# PSPS_AVNC_SRD_power-2020-10-14.net
KiCad netlist of a schematic drawn in EAGLE
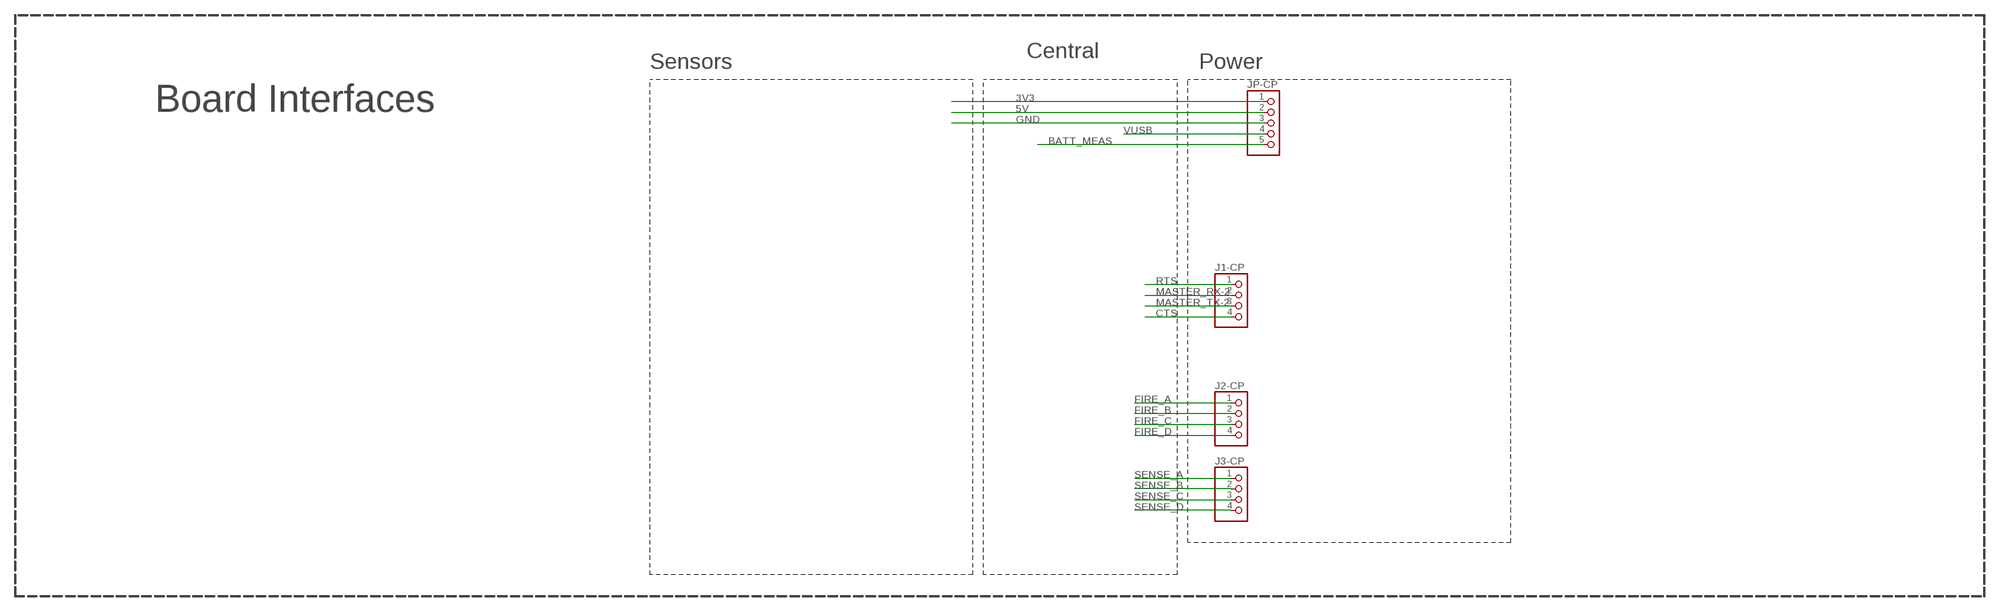
[diagram p0: schematic, sheet 1, part 1 of 3]
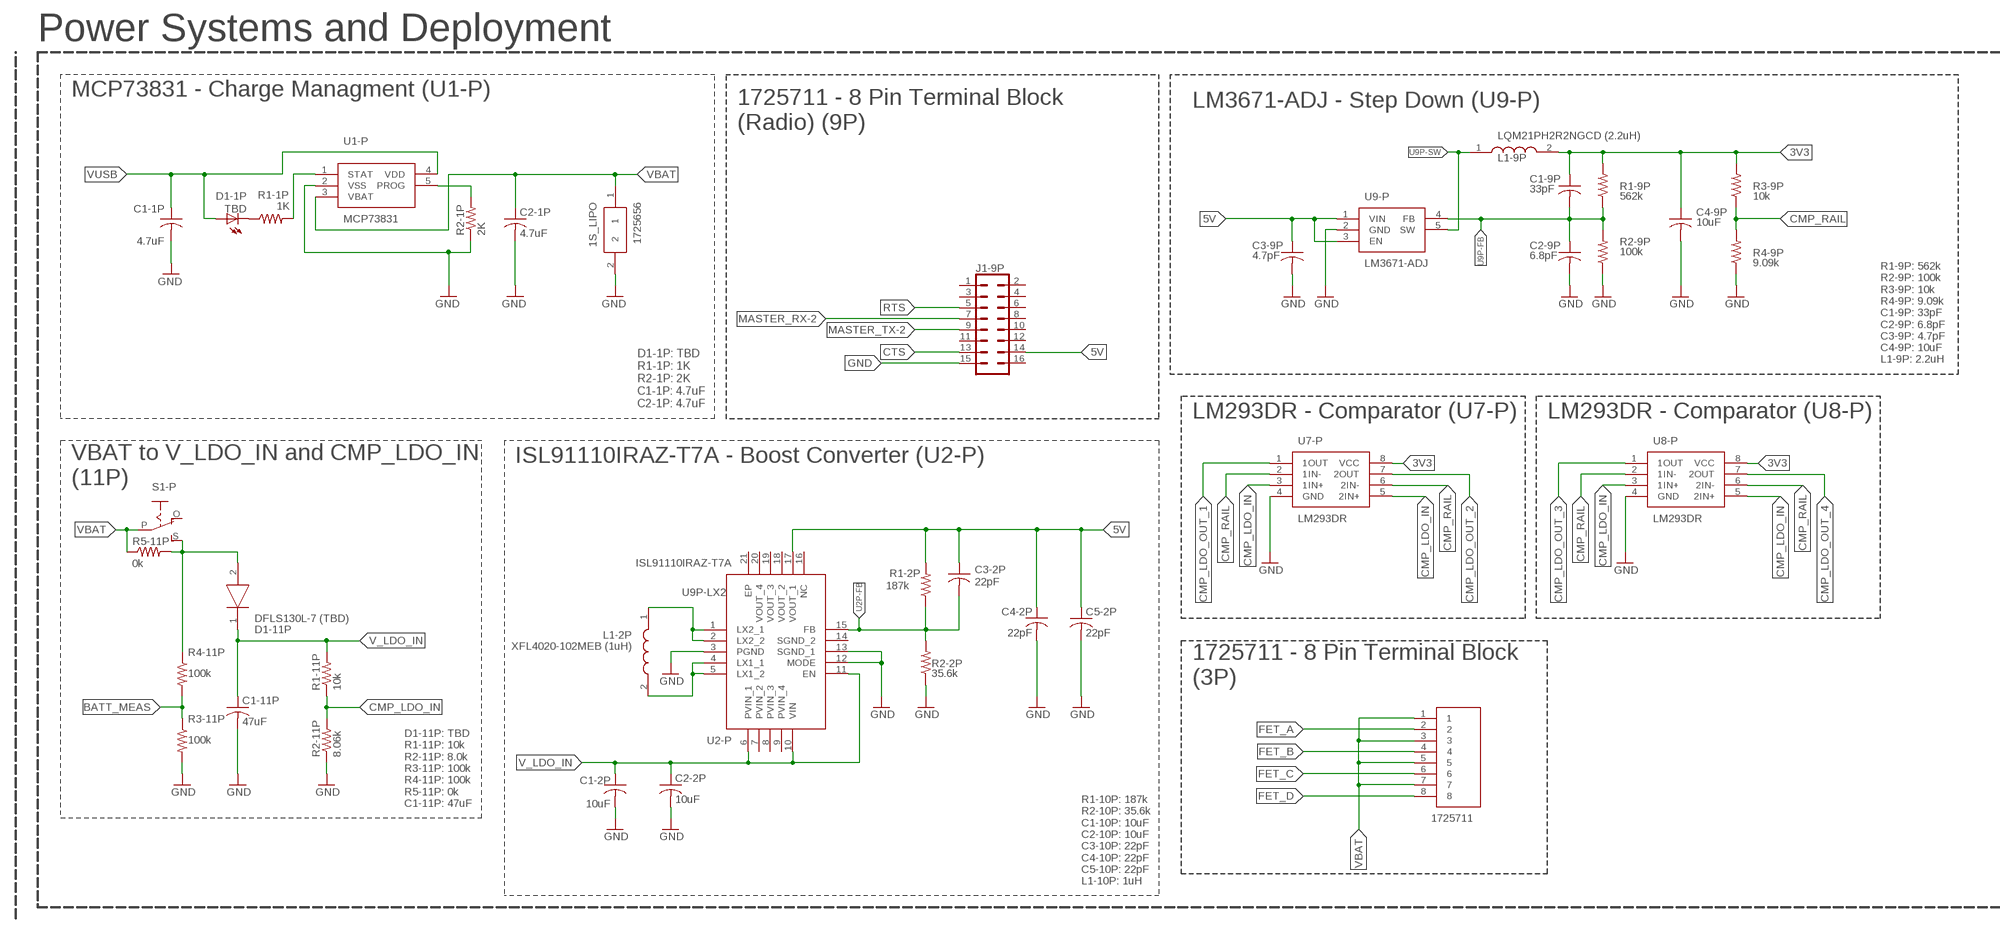
[diagram p1: schematic, sheet 1, part 2 of 3]
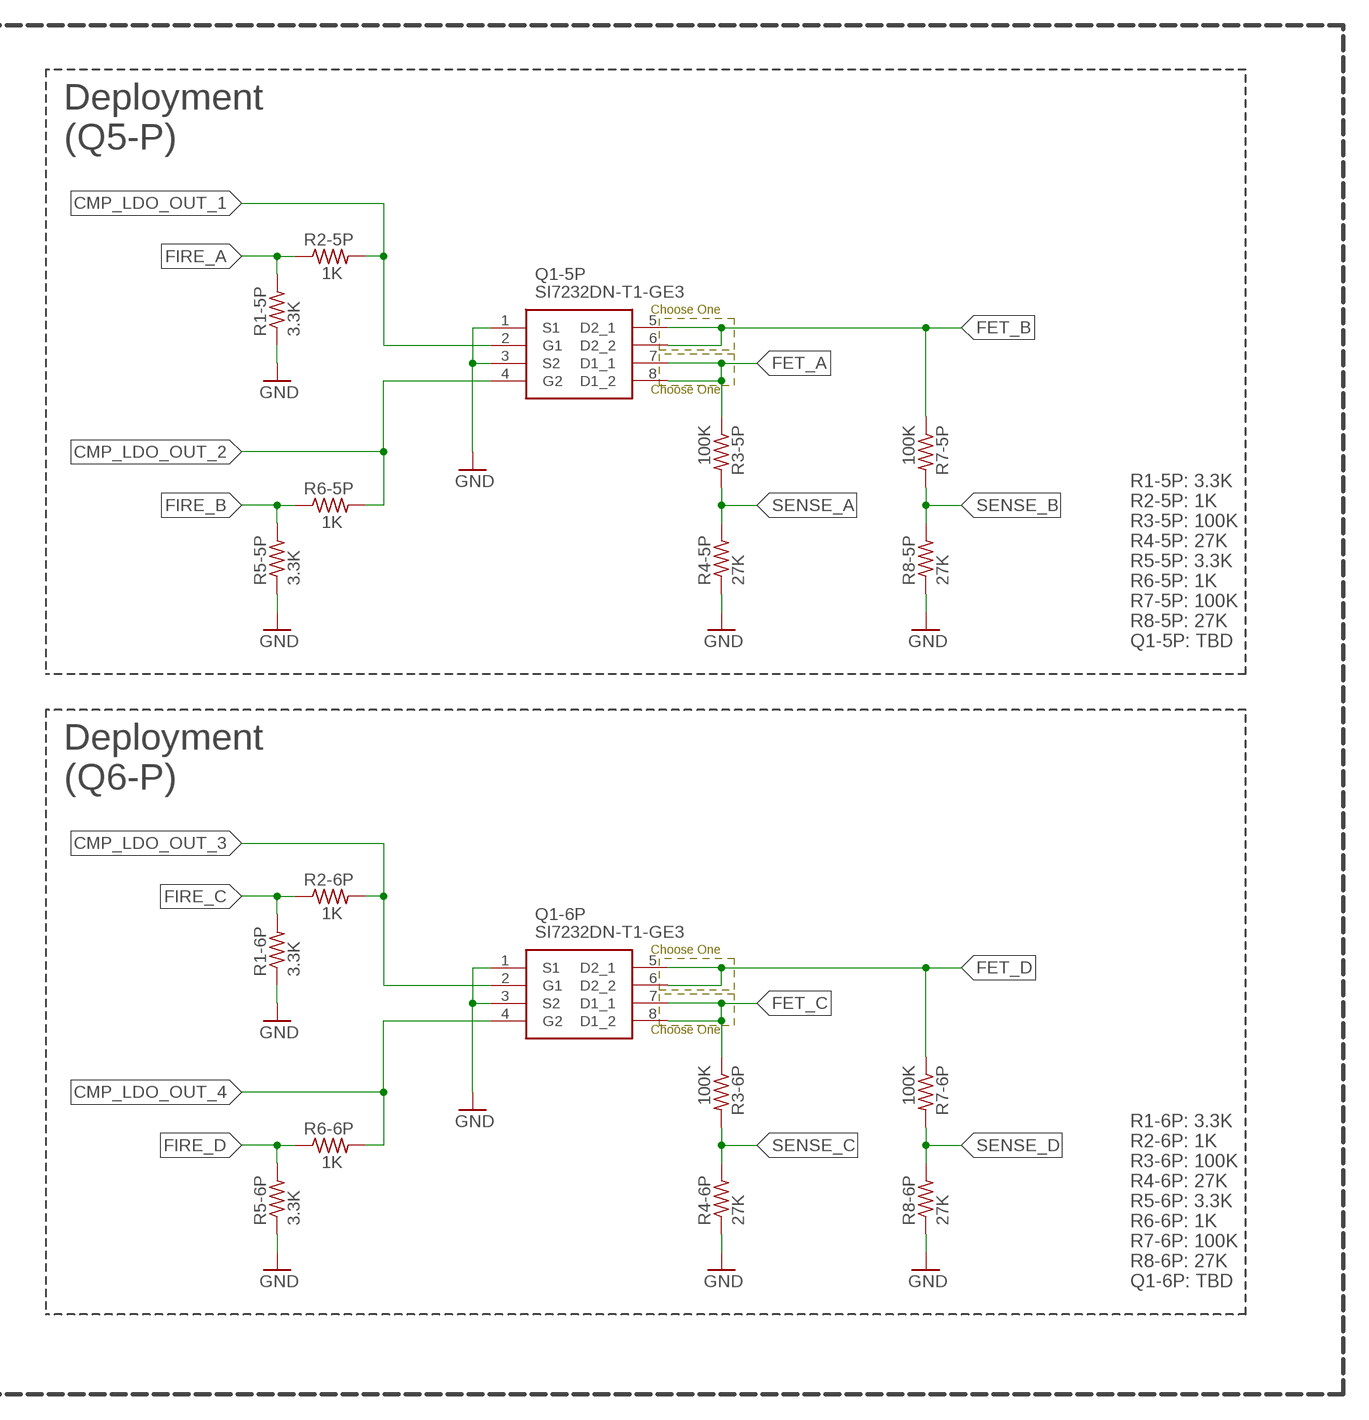
[diagram p2: schematic, sheet 1, part 3 of 3]

(export (version "E")
  (design (tool "Eeschema 10.0.6"))
  (components
    (comp (ref "1S_LIPO")
      (value "1725656")
      (footprint "eagle-import:1725656")
      (fields (field (name "MOUSER_PART_NUMBER") "651-1725656"))
      (libsource (lib "eagle-import") (part "1725656"))
    )
    (comp (ref "C1-1P")
      (value "4.7uF")
      (footprint "eagle-import:C0805")
      (libsource (lib "eagle-import") (part "resistor_348_C-USC0805"))
    )
    (comp (ref "C1-2P")
      (value "10uF")
      (footprint "eagle-import:C0805")
      (libsource (lib "eagle-import") (part "resistor_348_C-USC0805"))
    )
    (comp (ref "C1-9P")
      (value "33pF")
      (footprint "eagle-import:C0805")
      (libsource (lib "eagle-import") (part "resistor_348_C-USC0805"))
    )
    (comp (ref "C1-11P")
      (value "47uF")
      (footprint "eagle-import:C0805")
      (libsource (lib "eagle-import") (part "resistor_348_C-USC0805"))
    )
    (comp (ref "C2-1P")
      (value "4.7uF")
      (footprint "eagle-import:C0805")
      (libsource (lib "eagle-import") (part "resistor_348_C-USC0805"))
    )
    (comp (ref "C2-2P")
      (value "10uF")
      (footprint "eagle-import:C0805")
      (libsource (lib "eagle-import") (part "C-USC0805"))
    )
    (comp (ref "C2-9P")
      (value "6.8pF")
      (footprint "eagle-import:C0805")
      (libsource (lib "eagle-import") (part "resistor_348_C-USC0805"))
    )
    (comp (ref "C3-2P")
      (value "22pF")
      (footprint "eagle-import:C0805")
      (libsource (lib "eagle-import") (part "resistor_348_C-USC0805"))
    )
    (comp (ref "C3-9P")
      (value "4.7pF")
      (footprint "eagle-import:C0805")
      (libsource (lib "eagle-import") (part "resistor_348_C-USC0805"))
    )
    (comp (ref "C4-2P")
      (value "22pF")
      (footprint "eagle-import:C0805")
      (fields (field (name "SPICEPREFIX") "C"))
      (libsource (lib "eagle-import") (part "resistor_348_C-USC0805"))
    )
    (comp (ref "C4-9P")
      (value "10uF")
      (footprint "eagle-import:C0805")
      (libsource (lib "eagle-import") (part "resistor_348_C-USC0805"))
    )
    (comp (ref "C5-2P")
      (value "22pF")
      (footprint "eagle-import:C0805")
      (libsource (lib "eagle-import") (part "C-USC0805"))
    )
    (comp (ref "D1-1P")
      (value "TBD")
      (footprint "eagle-import:CHIPLED_0805")
      (libsource (lib "eagle-import") (part "LEDCHIPLED_0805"))
    )
    (comp (ref "D1-11P")
      (value "DFLS130L-7 (TBD)")
      (footprint "eagle-import:POWERDI_123")
      (fields
        (field (name "MANUFACTURER_PART_NUMBER") "DFLS130L-7")
        (field (name "MOUSER_PART_NUMBER") "621-DFLS130L")
      )
      (libsource (lib "eagle-import") (part "DFLS130L-7"))
    )
    (comp (ref "J1-9P")
      (value "CONN_08X2")
      (footprint "eagle-import:2X8")
      (libsource (lib "eagle-import") (part "CONN_08X2"))
    )
    (comp (ref "J1-CP")
      (value "PINHD-1X4")
      (footprint "eagle-import:1X04")
      (libsource (lib "eagle-import") (part "PINHD-1X4"))
    )
    (comp (ref "J2-CP")
      (value "PINHD-1X4")
      (footprint "eagle-import:1X04")
      (libsource (lib "eagle-import") (part "PINHD-1X4"))
    )
    (comp (ref "J2-P")
      (value "1725711")
      (footprint "eagle-import:1725711")
      (fields (field (name "MOUSER_PART_NUMBER") "651-1725711"))
      (libsource (lib "eagle-import") (part "1725711"))
    )
    (comp (ref "J3-CP")
      (value "PINHD-1X4")
      (footprint "eagle-import:1X04")
      (libsource (lib "eagle-import") (part "PINHD-1X4"))
    )
    (comp (ref "JP-CP")
      (value "PINHD-1X5")
      (footprint "eagle-import:1X05")
      (libsource (lib "eagle-import") (part "PINHD-1X5"))
    )
    (comp (ref "L1-2P")
      (value "XFL4020-102MEB (1uH)")
      (footprint "eagle-import:XFL4020")
      (fields
        (field (name "MANUFACTURER_PART_NUMBER") "XFL4020-102MEB")
        (field (name "MOUSER_PART_NUMBER") "994-XFL4020-102MEB")
      )
      (libsource (lib "eagle-import") (part "XFL4020-102MEB"))
    )
    (comp (ref "L1-9P")
      (value "LQM21PH2R2NGCD (2.2uH)")
      (footprint "eagle-import:INDC2012X100N")
      (fields
        (field (name "MANUFACTURER_PART_NUMBER") "LQM21PH2R2NGCD")
        (field (name "MOUSER_PART_NUMBER") "81-LQM21PH2R2NGCD")
      )
      (libsource (lib "eagle-import") (part "LQM21PH2R2NGCD"))
    )
    (comp (ref "Q1-5P")
      (value "SI7232DN-T1-GE3")
      (footprint "eagle-import:POWERPAK-1212-8")
      (fields (field (name "MOUSER_PART_NUMBER") "781-SI7232DN-GE3"))
      (libsource (lib "eagle-import") (part "SI7232DN-T1-GE3"))
    )
    (comp (ref "Q1-6P")
      (value "SI7232DN-T1-GE3")
      (footprint "eagle-import:POWERPAK-1212-8")
      (fields (field (name "MOUSER_PART_NUMBER") "781-SI7232DN-GE3"))
      (libsource (lib "eagle-import") (part "SI7232DN-T1-GE3"))
    )
    (comp (ref "R1-1P")
      (value "1K")
      (footprint "eagle-import:R0805")
      (libsource (lib "eagle-import") (part "resistor_348_R-US_R0805"))
    )
    (comp (ref "R1-2P")
      (value "187k")
      (footprint "eagle-import:R0805")
      (libsource (lib "eagle-import") (part "resistor_348_R-US_R0805"))
    )
    (comp (ref "R1-5P")
      (value "3.3K")
      (footprint "eagle-import:M0805")
      (libsource (lib "eagle-import") (part "rcl_334_R-US_M0805"))
    )
    (comp (ref "R1-6P")
      (value "3.3K")
      (footprint "eagle-import:M0805")
      (libsource (lib "eagle-import") (part "rcl_334_R-US_M0805"))
    )
    (comp (ref "R1-9P")
      (value "562k")
      (footprint "eagle-import:R0805")
      (libsource (lib "eagle-import") (part "resistor_348_R-US_R0805"))
    )
    (comp (ref "R1-11P")
      (value "10k")
      (footprint "eagle-import:R0805")
      (libsource (lib "eagle-import") (part "resistor_348_R-US_R0805"))
    )
    (comp (ref "R2-1P")
      (value "2K")
      (footprint "eagle-import:R0805")
      (libsource (lib "eagle-import") (part "resistor_348_R-US_R0805"))
    )
    (comp (ref "R2-2P")
      (value "35.6k")
      (footprint "eagle-import:R0805")
      (libsource (lib "eagle-import") (part "resistor_348_R-US_R0805"))
    )
    (comp (ref "R2-5P")
      (value "1K")
      (footprint "eagle-import:M0805")
      (libsource (lib "eagle-import") (part "rcl_334_R-US_M0805"))
    )
    (comp (ref "R2-6P")
      (value "1K")
      (footprint "eagle-import:M0805")
      (libsource (lib "eagle-import") (part "rcl_334_R-US_M0805"))
    )
    (comp (ref "R2-9P")
      (value "100k")
      (footprint "eagle-import:R0805")
      (libsource (lib "eagle-import") (part "resistor_348_R-US_R0805"))
    )
    (comp (ref "R2-11P")
      (value "8.06k")
      (footprint "eagle-import:R0805")
      (libsource (lib "eagle-import") (part "resistor_348_R-US_R0805"))
    )
    (comp (ref "R3-5P")
      (value "100K")
      (footprint "eagle-import:M0805")
      (libsource (lib "eagle-import") (part "rcl_334_R-US_M0805"))
    )
    (comp (ref "R3-6P")
      (value "100K")
      (footprint "eagle-import:M0805")
      (libsource (lib "eagle-import") (part "rcl_334_R-US_M0805"))
    )
    (comp (ref "R3-9P")
      (value "10k")
      (footprint "eagle-import:R0805")
      (libsource (lib "eagle-import") (part "resistor_348_R-US_R0805"))
    )
    (comp (ref "R3-11P")
      (value "100k")
      (footprint "eagle-import:R0805")
      (libsource (lib "eagle-import") (part "R-US_R0805"))
    )
    (comp (ref "R4-5P")
      (value "27K")
      (footprint "eagle-import:M0805")
      (libsource (lib "eagle-import") (part "rcl_334_R-US_M0805"))
    )
    (comp (ref "R4-6P")
      (value "27K")
      (footprint "eagle-import:M0805")
      (libsource (lib "eagle-import") (part "rcl_334_R-US_M0805"))
    )
    (comp (ref "R4-9P")
      (value "9.09k")
      (footprint "eagle-import:R0805")
      (libsource (lib "eagle-import") (part "resistor_348_R-US_R0805"))
    )
    (comp (ref "R4-11P")
      (value "100k")
      (footprint "eagle-import:R0805")
      (libsource (lib "eagle-import") (part "R-US_R0805"))
    )
    (comp (ref "R5-5P")
      (value "3.3K")
      (footprint "eagle-import:M0805")
      (libsource (lib "eagle-import") (part "rcl_334_R-US_M0805"))
    )
    (comp (ref "R5-6P")
      (value "3.3K")
      (footprint "eagle-import:M0805")
      (libsource (lib "eagle-import") (part "rcl_334_R-US_M0805"))
    )
    (comp (ref "R5-11P")
      (value "0k")
      (footprint "eagle-import:R0805")
      (libsource (lib "eagle-import") (part "R-US_R0805"))
    )
    (comp (ref "R6-5P")
      (value "1K")
      (footprint "eagle-import:M0805")
      (libsource (lib "eagle-import") (part "rcl_334_R-US_M0805"))
    )
    (comp (ref "R6-6P")
      (value "1K")
      (footprint "eagle-import:M0805")
      (libsource (lib "eagle-import") (part "rcl_334_R-US_M0805"))
    )
    (comp (ref "R7-5P")
      (value "100K")
      (footprint "eagle-import:M0805")
      (libsource (lib "eagle-import") (part "rcl_334_R-US_M0805"))
    )
    (comp (ref "R7-6P")
      (value "100K")
      (footprint "eagle-import:M0805")
      (libsource (lib "eagle-import") (part "rcl_334_R-US_M0805"))
    )
    (comp (ref "R8-5P")
      (value "27K")
      (footprint "eagle-import:M0805")
      (libsource (lib "eagle-import") (part "rcl_334_R-US_M0805"))
    )
    (comp (ref "R8-6P")
      (value "27K")
      (footprint "eagle-import:M0805")
      (libsource (lib "eagle-import") (part "rcl_334_R-US_M0805"))
    )
    (comp (ref "S1-P")
      (value "EG1218S")
      (footprint "eagle-import:EG1218")
      (libsource (lib "eagle-import") (part "EG1218S"))
    )
    (comp (ref "U1-P")
      (value "MCP73831")
      (footprint "eagle-import:SOT95P270X145-5N")
      (fields
        (field (name "MANUFACTURER_PART_NUMBER") "MCP73831T-2ACI/OT")
        (field (name "MOUSER_PART_NUMBER") "579-MCP73831T-2ACIOT")
      )
      (libsource (lib "eagle-import") (part "MCP73831T-2ACI_OT"))
    )
    (comp (ref "U2-P")
      (value "ISL91110IRAZ-T7A")
      (footprint "eagle-import:QFN50P400X400X100-21N")
      (libsource (lib "eagle-import") (part "ISL91110IRAZ-T7A"))
    )
    (comp (ref "U7-P")
      (value "LM293DR")
      (footprint "eagle-import:SOIC127P600X175-8N")
      (fields (field (name "MOUSER_PART_NUMBER") "595-LM293DR"))
      (libsource (lib "eagle-import") (part "LM293DR"))
    )
    (comp (ref "U8-P")
      (value "LM293DR")
      (footprint "eagle-import:SOIC127P600X175-8N")
      (fields (field (name "MOUSER_PART_NUMBER") "595-LM293DR"))
      (libsource (lib "eagle-import") (part "LM293DR"))
    )
    (comp (ref "U9-P")
      (value "LM3671-ADJ")
      (footprint "eagle-import:SOT95P280X145-5N")
      (fields
        (field (name "MANUFACTURER_PART_NUMBER") "LM3671MFX-ADJ/NOPB")
        (field (name "MOUSER_PART_NUMBER") "926-LM3671MFXADJNOPB")
      )
      (libsource (lib "eagle-import") (part "LM3671MFX-ADJ_NOPB"))
    )
  )
  (nets
    (net (code "1") (name "/U9P-LX2") (class "Default")
      (node (ref "L1-2P") (pin "1") (pinfunction "1_1") (pintype "bidirectional"))
      (node (ref "U2-P") (pin "1") (pinfunction "LX2_1_1") (pintype "bidirectional"))
      (node (ref "U2-P") (pin "2") (pinfunction "LX2_2_2") (pintype "bidirectional"))
    )
    (net (code "2") (name "3V3") (class "Default")
      (node (ref "C1-9P") (pin "1") (pinfunction "1_1") (pintype "passive"))
      (node (ref "C4-9P") (pin "1") (pinfunction "1_1") (pintype "passive"))
      (node (ref "JP-CP") (pin "1") (pinfunction "1_1") (pintype "passive"))
      (node (ref "L1-9P") (pin "2") (pinfunction "2_2") (pintype "bidirectional"))
      (node (ref "R1-9P") (pin "2") (pinfunction "2_2") (pintype "passive"))
      (node (ref "R3-9P") (pin "2") (pinfunction "2_2") (pintype "passive"))
      (node (ref "U7-P") (pin "8") (pinfunction "VCC_8") (pintype "bidirectional"))
      (node (ref "U8-P") (pin "8") (pinfunction "VCC_8") (pintype "bidirectional"))
    )
    (net (code "3") (name "5V") (class "Default")
      (node (ref "C3-2P") (pin "1") (pinfunction "1_1") (pintype "passive"))
      (node (ref "C3-9P") (pin "1") (pinfunction "1_1") (pintype "passive"))
      (node (ref "C4-2P") (pin "1") (pinfunction "1_1") (pintype "passive"))
      (node (ref "C5-2P") (pin "1") (pinfunction "1_1") (pintype "passive"))
      (node (ref "J1-9P") (pin "14") (pinfunction "14_14") (pintype "passive"))
      (node (ref "JP-CP") (pin "2") (pinfunction "2_2") (pintype "passive"))
      (node (ref "R1-2P") (pin "2") (pinfunction "2_2") (pintype "passive"))
      (node (ref "U2-P") (pin "17") (pinfunction "VOUT_1_17") (pintype "bidirectional"))
      (node (ref "U9-P") (pin "1") (pinfunction "VIN_1") (pintype "bidirectional"))
      (node (ref "U9-P") (pin "3") (pinfunction "EN_3") (pintype "bidirectional"))
    )
    (net (code "4") (name "BATT_MEAS") (class "Default")
      (node (ref "JP-CP") (pin "5") (pinfunction "5_5") (pintype "passive"))
      (node (ref "R3-11P") (pin "1") (pinfunction "1_1") (pintype "passive"))
      (node (ref "R4-11P") (pin "2") (pinfunction "2_2") (pintype "passive"))
    )
    (net (code "5") (name "CMP_LDO_IN") (class "Default")
      (node (ref "R1-11P") (pin "1") (pinfunction "1_1") (pintype "passive"))
      (node (ref "R2-11P") (pin "2") (pinfunction "2_2") (pintype "passive"))
      (node (ref "U7-P") (pin "3") (pinfunction "1IN+_3") (pintype "bidirectional"))
      (node (ref "U7-P") (pin "5") (pinfunction "2IN+_5") (pintype "bidirectional"))
      (node (ref "U8-P") (pin "3") (pinfunction "1IN+_3") (pintype "bidirectional"))
      (node (ref "U8-P") (pin "5") (pinfunction "2IN+_5") (pintype "bidirectional"))
    )
    (net (code "6") (name "CMP_LDO_OUT_1") (class "Default")
      (node (ref "Q1-5P") (pin "2") (pinfunction "G1_2") (pintype "bidirectional"))
      (node (ref "R2-5P") (pin "2") (pinfunction "2_2") (pintype "passive"))
      (node (ref "U7-P") (pin "1") (pinfunction "1OUT_1") (pintype "bidirectional"))
    )
    (net (code "7") (name "CMP_LDO_OUT_2") (class "Default")
      (node (ref "Q1-5P") (pin "4") (pinfunction "G2_4") (pintype "bidirectional"))
      (node (ref "R6-5P") (pin "2") (pinfunction "2_2") (pintype "passive"))
      (node (ref "U7-P") (pin "7") (pinfunction "2OUT_7") (pintype "bidirectional"))
    )
    (net (code "8") (name "CMP_LDO_OUT_3") (class "Default")
      (node (ref "Q1-6P") (pin "2") (pinfunction "G1_2") (pintype "bidirectional"))
      (node (ref "R2-6P") (pin "2") (pinfunction "2_2") (pintype "passive"))
      (node (ref "U8-P") (pin "1") (pinfunction "1OUT_1") (pintype "bidirectional"))
    )
    (net (code "9") (name "CMP_LDO_OUT_4") (class "Default")
      (node (ref "Q1-6P") (pin "4") (pinfunction "G2_4") (pintype "bidirectional"))
      (node (ref "R6-6P") (pin "2") (pinfunction "2_2") (pintype "passive"))
      (node (ref "U8-P") (pin "7") (pinfunction "2OUT_7") (pintype "bidirectional"))
    )
    (net (code "10") (name "CMP_RAIL") (class "Default")
      (node (ref "R3-9P") (pin "1") (pinfunction "1_1") (pintype "passive"))
      (node (ref "R4-9P") (pin "2") (pinfunction "2_2") (pintype "passive"))
      (node (ref "U7-P") (pin "2") (pinfunction "1IN-_2") (pintype "bidirectional"))
      (node (ref "U7-P") (pin "6") (pinfunction "2IN-_6") (pintype "bidirectional"))
      (node (ref "U8-P") (pin "2") (pinfunction "1IN-_2") (pintype "bidirectional"))
      (node (ref "U8-P") (pin "6") (pinfunction "2IN-_6") (pintype "bidirectional"))
    )
    (net (code "11") (name "CTS") (class "Default")
      (node (ref "J1-9P") (pin "13") (pinfunction "13_13") (pintype "passive"))
      (node (ref "J1-CP") (pin "4") (pinfunction "4_4") (pintype "passive"))
    )
    (net (code "12") (name "FET_A") (class "Default")
      (node (ref "J2-P") (pin "2") (pinfunction "2_2") (pintype "bidirectional"))
      (node (ref "Q1-5P") (pin "7") (pinfunction "D1_1_7") (pintype "bidirectional"))
      (node (ref "Q1-5P") (pin "8") (pinfunction "D1_2_8") (pintype "bidirectional"))
      (node (ref "R3-5P") (pin "1") (pinfunction "1_1") (pintype "passive"))
    )
    (net (code "13") (name "FET_B") (class "Default")
      (node (ref "J2-P") (pin "4") (pinfunction "4_4") (pintype "bidirectional"))
      (node (ref "Q1-5P") (pin "5") (pinfunction "D2_1_5") (pintype "bidirectional"))
      (node (ref "Q1-5P") (pin "6") (pinfunction "D2_2_6") (pintype "bidirectional"))
      (node (ref "R7-5P") (pin "1") (pinfunction "1_1") (pintype "passive"))
    )
    (net (code "14") (name "FET_C") (class "Default")
      (node (ref "J2-P") (pin "6") (pinfunction "6_6") (pintype "bidirectional"))
      (node (ref "Q1-6P") (pin "7") (pinfunction "D1_1_7") (pintype "bidirectional"))
      (node (ref "Q1-6P") (pin "8") (pinfunction "D1_2_8") (pintype "bidirectional"))
      (node (ref "R3-6P") (pin "1") (pinfunction "1_1") (pintype "passive"))
    )
    (net (code "15") (name "FET_D") (class "Default")
      (node (ref "J2-P") (pin "8") (pinfunction "8_8") (pintype "bidirectional"))
      (node (ref "Q1-6P") (pin "5") (pinfunction "D2_1_5") (pintype "bidirectional"))
      (node (ref "Q1-6P") (pin "6") (pinfunction "D2_2_6") (pintype "bidirectional"))
      (node (ref "R7-6P") (pin "1") (pinfunction "1_1") (pintype "passive"))
    )
    (net (code "16") (name "FIRE_A") (class "Default")
      (node (ref "J2-CP") (pin "1") (pinfunction "1_1") (pintype "passive"))
      (node (ref "R1-5P") (pin "2") (pinfunction "2_2") (pintype "passive"))
      (node (ref "R2-5P") (pin "1") (pinfunction "1_1") (pintype "passive"))
    )
    (net (code "17") (name "FIRE_B") (class "Default")
      (node (ref "J2-CP") (pin "2") (pinfunction "2_2") (pintype "passive"))
      (node (ref "R5-5P") (pin "2") (pinfunction "2_2") (pintype "passive"))
      (node (ref "R6-5P") (pin "1") (pinfunction "1_1") (pintype "passive"))
    )
    (net (code "18") (name "FIRE_C") (class "Default")
      (node (ref "J2-CP") (pin "3") (pinfunction "3_3") (pintype "passive"))
      (node (ref "R1-6P") (pin "2") (pinfunction "2_2") (pintype "passive"))
      (node (ref "R2-6P") (pin "1") (pinfunction "1_1") (pintype "passive"))
    )
    (net (code "19") (name "FIRE_D") (class "Default")
      (node (ref "J2-CP") (pin "4") (pinfunction "4_4") (pintype "passive"))
      (node (ref "R5-6P") (pin "2") (pinfunction "2_2") (pintype "passive"))
      (node (ref "R6-6P") (pin "1") (pinfunction "1_1") (pintype "passive"))
    )
    (net (code "20") (name "GND") (class "Default")
      (node (ref "1S_LIPO") (pin "2") (pinfunction "2_2") (pintype "bidirectional"))
      (node (ref "C1-11P") (pin "2") (pinfunction "2_2") (pintype "passive"))
      (node (ref "C1-1P") (pin "2") (pinfunction "2_2") (pintype "passive"))
      (node (ref "C1-2P") (pin "2") (pinfunction "2_2") (pintype "passive"))
      (node (ref "C2-1P") (pin "2") (pinfunction "2_2") (pintype "passive"))
      (node (ref "C2-2P") (pin "2") (pinfunction "2_2") (pintype "passive"))
      (node (ref "C2-9P") (pin "2") (pinfunction "2_2") (pintype "passive"))
      (node (ref "C3-9P") (pin "2") (pinfunction "2_2") (pintype "passive"))
      (node (ref "C4-2P") (pin "2") (pinfunction "2_2") (pintype "passive"))
      (node (ref "C4-9P") (pin "2") (pinfunction "2_2") (pintype "passive"))
      (node (ref "C5-2P") (pin "2") (pinfunction "2_2") (pintype "passive"))
      (node (ref "J1-9P") (pin "15") (pinfunction "15_15") (pintype "passive"))
      (node (ref "JP-CP") (pin "3") (pinfunction "3_3") (pintype "passive"))
      (node (ref "Q1-5P") (pin "1") (pinfunction "S1_1") (pintype "bidirectional"))
      (node (ref "Q1-5P") (pin "3") (pinfunction "S2_3") (pintype "bidirectional"))
      (node (ref "Q1-6P") (pin "1") (pinfunction "S1_1") (pintype "bidirectional"))
      (node (ref "Q1-6P") (pin "3") (pinfunction "S2_3") (pintype "bidirectional"))
      (node (ref "R1-5P") (pin "1") (pinfunction "1_1") (pintype "passive"))
      (node (ref "R1-6P") (pin "1") (pinfunction "1_1") (pintype "passive"))
      (node (ref "R2-11P") (pin "1") (pinfunction "1_1") (pintype "passive"))
      (node (ref "R2-1P") (pin "1") (pinfunction "1_1") (pintype "passive"))
      (node (ref "R2-2P") (pin "1") (pinfunction "1_1") (pintype "passive"))
      (node (ref "R2-9P") (pin "1") (pinfunction "1_1") (pintype "passive"))
      (node (ref "R3-11P") (pin "2") (pinfunction "2_2") (pintype "passive"))
      (node (ref "R4-5P") (pin "1") (pinfunction "1_1") (pintype "passive"))
      (node (ref "R4-6P") (pin "1") (pinfunction "1_1") (pintype "passive"))
      (node (ref "R4-9P") (pin "1") (pinfunction "1_1") (pintype "passive"))
      (node (ref "R5-5P") (pin "1") (pinfunction "1_1") (pintype "passive"))
      (node (ref "R5-6P") (pin "1") (pinfunction "1_1") (pintype "passive"))
      (node (ref "R8-5P") (pin "1") (pinfunction "1_1") (pintype "passive"))
      (node (ref "R8-6P") (pin "1") (pinfunction "1_1") (pintype "passive"))
      (node (ref "U1-P") (pin "2") (pinfunction "VSS_2") (pintype "bidirectional"))
      (node (ref "U2-P") (pin "12") (pinfunction "MODE_12") (pintype "bidirectional"))
      (node (ref "U2-P") (pin "13") (pinfunction "SGND_1_13") (pintype "bidirectional"))
      (node (ref "U2-P") (pin "3") (pinfunction "PGND_3") (pintype "bidirectional"))
      (node (ref "U7-P") (pin "4") (pinfunction "GND_4") (pintype "bidirectional"))
      (node (ref "U8-P") (pin "4") (pinfunction "GND_4") (pintype "bidirectional"))
      (node (ref "U9-P") (pin "2") (pinfunction "GND_2") (pintype "bidirectional"))
    )
    (net (code "21") (name "MASTER_RX-2") (class "Default")
      (node (ref "J1-9P") (pin "7") (pinfunction "7_7") (pintype "passive"))
      (node (ref "J1-CP") (pin "2") (pinfunction "2_2") (pintype "passive"))
    )
    (net (code "22") (name "MASTER_TX-2") (class "Default")
      (node (ref "J1-9P") (pin "9") (pinfunction "9_9") (pintype "passive"))
      (node (ref "J1-CP") (pin "3") (pinfunction "3_3") (pintype "passive"))
    )
    (net (code "23") (name "Net-(D1-1P-PadC)") (class "Default")
      (node (ref "D1-1P") (pin "C") (pinfunction "C_C") (pintype "passive"))
      (node (ref "R1-1P") (pin "1") (pinfunction "1_1") (pintype "passive"))
    )
    (net (code "24") (name "Net-(D1-11P-A)") (class "Default")
      (node (ref "D1-11P") (pin "2") (pinfunction "A_2") (pintype "bidirectional"))
      (node (ref "R4-11P") (pin "1") (pinfunction "1_1") (pintype "passive"))
      (node (ref "R5-11P") (pin "2") (pinfunction "2_2") (pintype "passive"))
      (node (ref "S1-P") (pin "S") (pinfunction "S_S") (pintype "passive"))
    )
    (net (code "25") (name "Net-(U1-P-PROG)") (class "Default")
      (node (ref "R2-1P") (pin "2") (pinfunction "2_2") (pintype "passive"))
      (node (ref "U1-P") (pin "5") (pinfunction "PROG_5") (pintype "bidirectional"))
    )
    (net (code "26") (name "Net-(U1-P-STAT)") (class "Default")
      (node (ref "R1-1P") (pin "2") (pinfunction "2_2") (pintype "passive"))
      (node (ref "U1-P") (pin "1") (pinfunction "STAT_1") (pintype "bidirectional"))
    )
    (net (code "27") (name "Net-(U2-P-LX1_1)") (class "Default")
      (node (ref "L1-2P") (pin "2") (pinfunction "2_2") (pintype "bidirectional"))
      (node (ref "U2-P") (pin "4") (pinfunction "LX1_1_4") (pintype "bidirectional"))
      (node (ref "U2-P") (pin "5") (pinfunction "LX1_2_5") (pintype "bidirectional"))
    )
    (net (code "28") (name "RTS") (class "Default")
      (node (ref "J1-9P") (pin "5") (pinfunction "5_5") (pintype "passive"))
      (node (ref "J1-CP") (pin "1") (pinfunction "1_1") (pintype "passive"))
    )
    (net (code "29") (name "SENSE_A") (class "Default")
      (node (ref "J3-CP") (pin "1") (pinfunction "1_1") (pintype "passive"))
      (node (ref "R3-5P") (pin "2") (pinfunction "2_2") (pintype "passive"))
      (node (ref "R4-5P") (pin "2") (pinfunction "2_2") (pintype "passive"))
    )
    (net (code "30") (name "SENSE_B") (class "Default")
      (node (ref "J3-CP") (pin "2") (pinfunction "2_2") (pintype "passive"))
      (node (ref "R7-5P") (pin "2") (pinfunction "2_2") (pintype "passive"))
      (node (ref "R8-5P") (pin "2") (pinfunction "2_2") (pintype "passive"))
    )
    (net (code "31") (name "SENSE_C") (class "Default")
      (node (ref "J3-CP") (pin "3") (pinfunction "3_3") (pintype "passive"))
      (node (ref "R3-6P") (pin "2") (pinfunction "2_2") (pintype "passive"))
      (node (ref "R4-6P") (pin "2") (pinfunction "2_2") (pintype "passive"))
    )
    (net (code "32") (name "SENSE_D") (class "Default")
      (node (ref "J3-CP") (pin "4") (pinfunction "4_4") (pintype "passive"))
      (node (ref "R7-6P") (pin "2") (pinfunction "2_2") (pintype "passive"))
      (node (ref "R8-6P") (pin "2") (pinfunction "2_2") (pintype "passive"))
    )
    (net (code "33") (name "U2P-FB") (class "Default")
      (node (ref "C3-2P") (pin "2") (pinfunction "2_2") (pintype "passive"))
      (node (ref "R1-2P") (pin "1") (pinfunction "1_1") (pintype "passive"))
      (node (ref "R2-2P") (pin "2") (pinfunction "2_2") (pintype "passive"))
      (node (ref "U2-P") (pin "15") (pinfunction "FB_15") (pintype "bidirectional"))
    )
    (net (code "34") (name "U9P-FB") (class "Default")
      (node (ref "C1-9P") (pin "2") (pinfunction "2_2") (pintype "passive"))
      (node (ref "C2-9P") (pin "1") (pinfunction "1_1") (pintype "passive"))
      (node (ref "R1-9P") (pin "1") (pinfunction "1_1") (pintype "passive"))
      (node (ref "R2-9P") (pin "2") (pinfunction "2_2") (pintype "passive"))
      (node (ref "U9-P") (pin "4") (pinfunction "FB_4") (pintype "bidirectional"))
    )
    (net (code "35") (name "U9P-SW") (class "Default")
      (node (ref "L1-9P") (pin "1") (pinfunction "1_1") (pintype "bidirectional"))
      (node (ref "U9-P") (pin "5") (pinfunction "SW_5") (pintype "bidirectional"))
    )
    (net (code "36") (name "VBAT") (class "Default")
      (node (ref "1S_LIPO") (pin "1") (pinfunction "1_1") (pintype "bidirectional"))
      (node (ref "C2-1P") (pin "1") (pinfunction "1_1") (pintype "passive"))
      (node (ref "J2-P") (pin "1") (pinfunction "1_1") (pintype "bidirectional"))
      (node (ref "J2-P") (pin "3") (pinfunction "3_3") (pintype "bidirectional"))
      (node (ref "J2-P") (pin "5") (pinfunction "5_5") (pintype "bidirectional"))
      (node (ref "J2-P") (pin "7") (pinfunction "7_7") (pintype "bidirectional"))
      (node (ref "R5-11P") (pin "1") (pinfunction "1_1") (pintype "passive"))
      (node (ref "S1-P") (pin "P") (pinfunction "P_P") (pintype "passive"))
      (node (ref "U1-P") (pin "3") (pinfunction "VBAT_3") (pintype "bidirectional"))
    )
    (net (code "37") (name "VUSB") (class "Default")
      (node (ref "C1-1P") (pin "1") (pinfunction "1_1") (pintype "passive"))
      (node (ref "D1-1P") (pin "A") (pinfunction "A_A") (pintype "passive"))
      (node (ref "JP-CP") (pin "4") (pinfunction "4_4") (pintype "passive"))
      (node (ref "U1-P") (pin "4") (pinfunction "VDD_4") (pintype "bidirectional"))
    )
    (net (code "38") (name "V_LDO_IN") (class "Default")
      (node (ref "C1-11P") (pin "1") (pinfunction "1_1") (pintype "passive"))
      (node (ref "C1-2P") (pin "1") (pinfunction "1_1") (pintype "passive"))
      (node (ref "C2-2P") (pin "1") (pinfunction "1_1") (pintype "passive"))
      (node (ref "D1-11P") (pin "1") (pinfunction "K_1") (pintype "bidirectional"))
      (node (ref "R1-11P") (pin "2") (pinfunction "2_2") (pintype "passive"))
      (node (ref "U2-P") (pin "10") (pinfunction "VIN_10") (pintype "bidirectional"))
      (node (ref "U2-P") (pin "11") (pinfunction "EN_11") (pintype "bidirectional"))
      (node (ref "U2-P") (pin "6") (pinfunction "PVIN_1_6") (pintype "bidirectional"))
    )
    (net (code "39") (name "unconnected-(J1-9P-Pad1)") (class "Default")
      (node (ref "J1-9P") (pin "1") (pinfunction "1_1") (pintype "passive"))
    )
    (net (code "40") (name "unconnected-(J1-9P-Pad2)") (class "Default")
      (node (ref "J1-9P") (pin "2") (pinfunction "2_2") (pintype "passive"))
    )
    (net (code "41") (name "unconnected-(J1-9P-Pad3)") (class "Default")
      (node (ref "J1-9P") (pin "3") (pinfunction "3_3") (pintype "passive"))
    )
    (net (code "42") (name "unconnected-(J1-9P-Pad4)") (class "Default")
      (node (ref "J1-9P") (pin "4") (pinfunction "4_4") (pintype "passive"))
    )
    (net (code "43") (name "unconnected-(J1-9P-Pad6)") (class "Default")
      (node (ref "J1-9P") (pin "6") (pinfunction "6_6") (pintype "passive"))
    )
    (net (code "44") (name "unconnected-(J1-9P-Pad8)") (class "Default")
      (node (ref "J1-9P") (pin "8") (pinfunction "8_8") (pintype "passive"))
    )
    (net (code "45") (name "unconnected-(J1-9P-Pad10)") (class "Default")
      (node (ref "J1-9P") (pin "10") (pinfunction "10_10") (pintype "passive"))
    )
    (net (code "46") (name "unconnected-(J1-9P-Pad11)") (class "Default")
      (node (ref "J1-9P") (pin "11") (pinfunction "11_11") (pintype "passive"))
    )
    (net (code "47") (name "unconnected-(J1-9P-Pad12)") (class "Default")
      (node (ref "J1-9P") (pin "12") (pinfunction "12_12") (pintype "passive"))
    )
    (net (code "48") (name "unconnected-(J1-9P-Pad16)") (class "Default")
      (node (ref "J1-9P") (pin "16") (pinfunction "16_16") (pintype "passive"))
    )
    (net (code "49") (name "unconnected-(S1-P-PadO)") (class "Default")
      (node (ref "S1-P") (pin "O") (pinfunction "O_O") (pintype "passive"))
    )
    (net (code "50") (name "unconnected-(U2-P-EP-Pad21)") (class "Default")
      (node (ref "U2-P") (pin "21") (pinfunction "EP_21") (pintype "bidirectional"))
    )
    (net (code "51") (name "unconnected-(U2-P-NC-Pad16)") (class "Default")
      (node (ref "U2-P") (pin "16") (pinfunction "NC_16") (pintype "no_connect"))
    )
    (net (code "52") (name "unconnected-(U2-P-PVIN_2-Pad7)") (class "Default")
      (node (ref "U2-P") (pin "7") (pinfunction "PVIN_2_7") (pintype "bidirectional"))
    )
    (net (code "53") (name "unconnected-(U2-P-PVIN_3-Pad8)") (class "Default")
      (node (ref "U2-P") (pin "8") (pinfunction "PVIN_3_8") (pintype "bidirectional"))
    )
    (net (code "54") (name "unconnected-(U2-P-PVIN_4-Pad9)") (class "Default")
      (node (ref "U2-P") (pin "9") (pinfunction "PVIN_4_9") (pintype "bidirectional"))
    )
    (net (code "55") (name "unconnected-(U2-P-SGND_2-Pad14)") (class "Default")
      (node (ref "U2-P") (pin "14") (pinfunction "SGND_2_14") (pintype "bidirectional"))
    )
    (net (code "56") (name "unconnected-(U2-P-VOUT_2-Pad18)") (class "Default")
      (node (ref "U2-P") (pin "18") (pinfunction "VOUT_2_18") (pintype "bidirectional"))
    )
    (net (code "57") (name "unconnected-(U2-P-VOUT_3-Pad19)") (class "Default")
      (node (ref "U2-P") (pin "19") (pinfunction "VOUT_3_19") (pintype "bidirectional"))
    )
    (net (code "58") (name "unconnected-(U2-P-VOUT_4-Pad20)") (class "Default")
      (node (ref "U2-P") (pin "20") (pinfunction "VOUT_4_20") (pintype "bidirectional"))
    )
  )
)
